# Wilssen_core_v0_205a.net
KiCad netlist of a schematic drawn in EAGLE
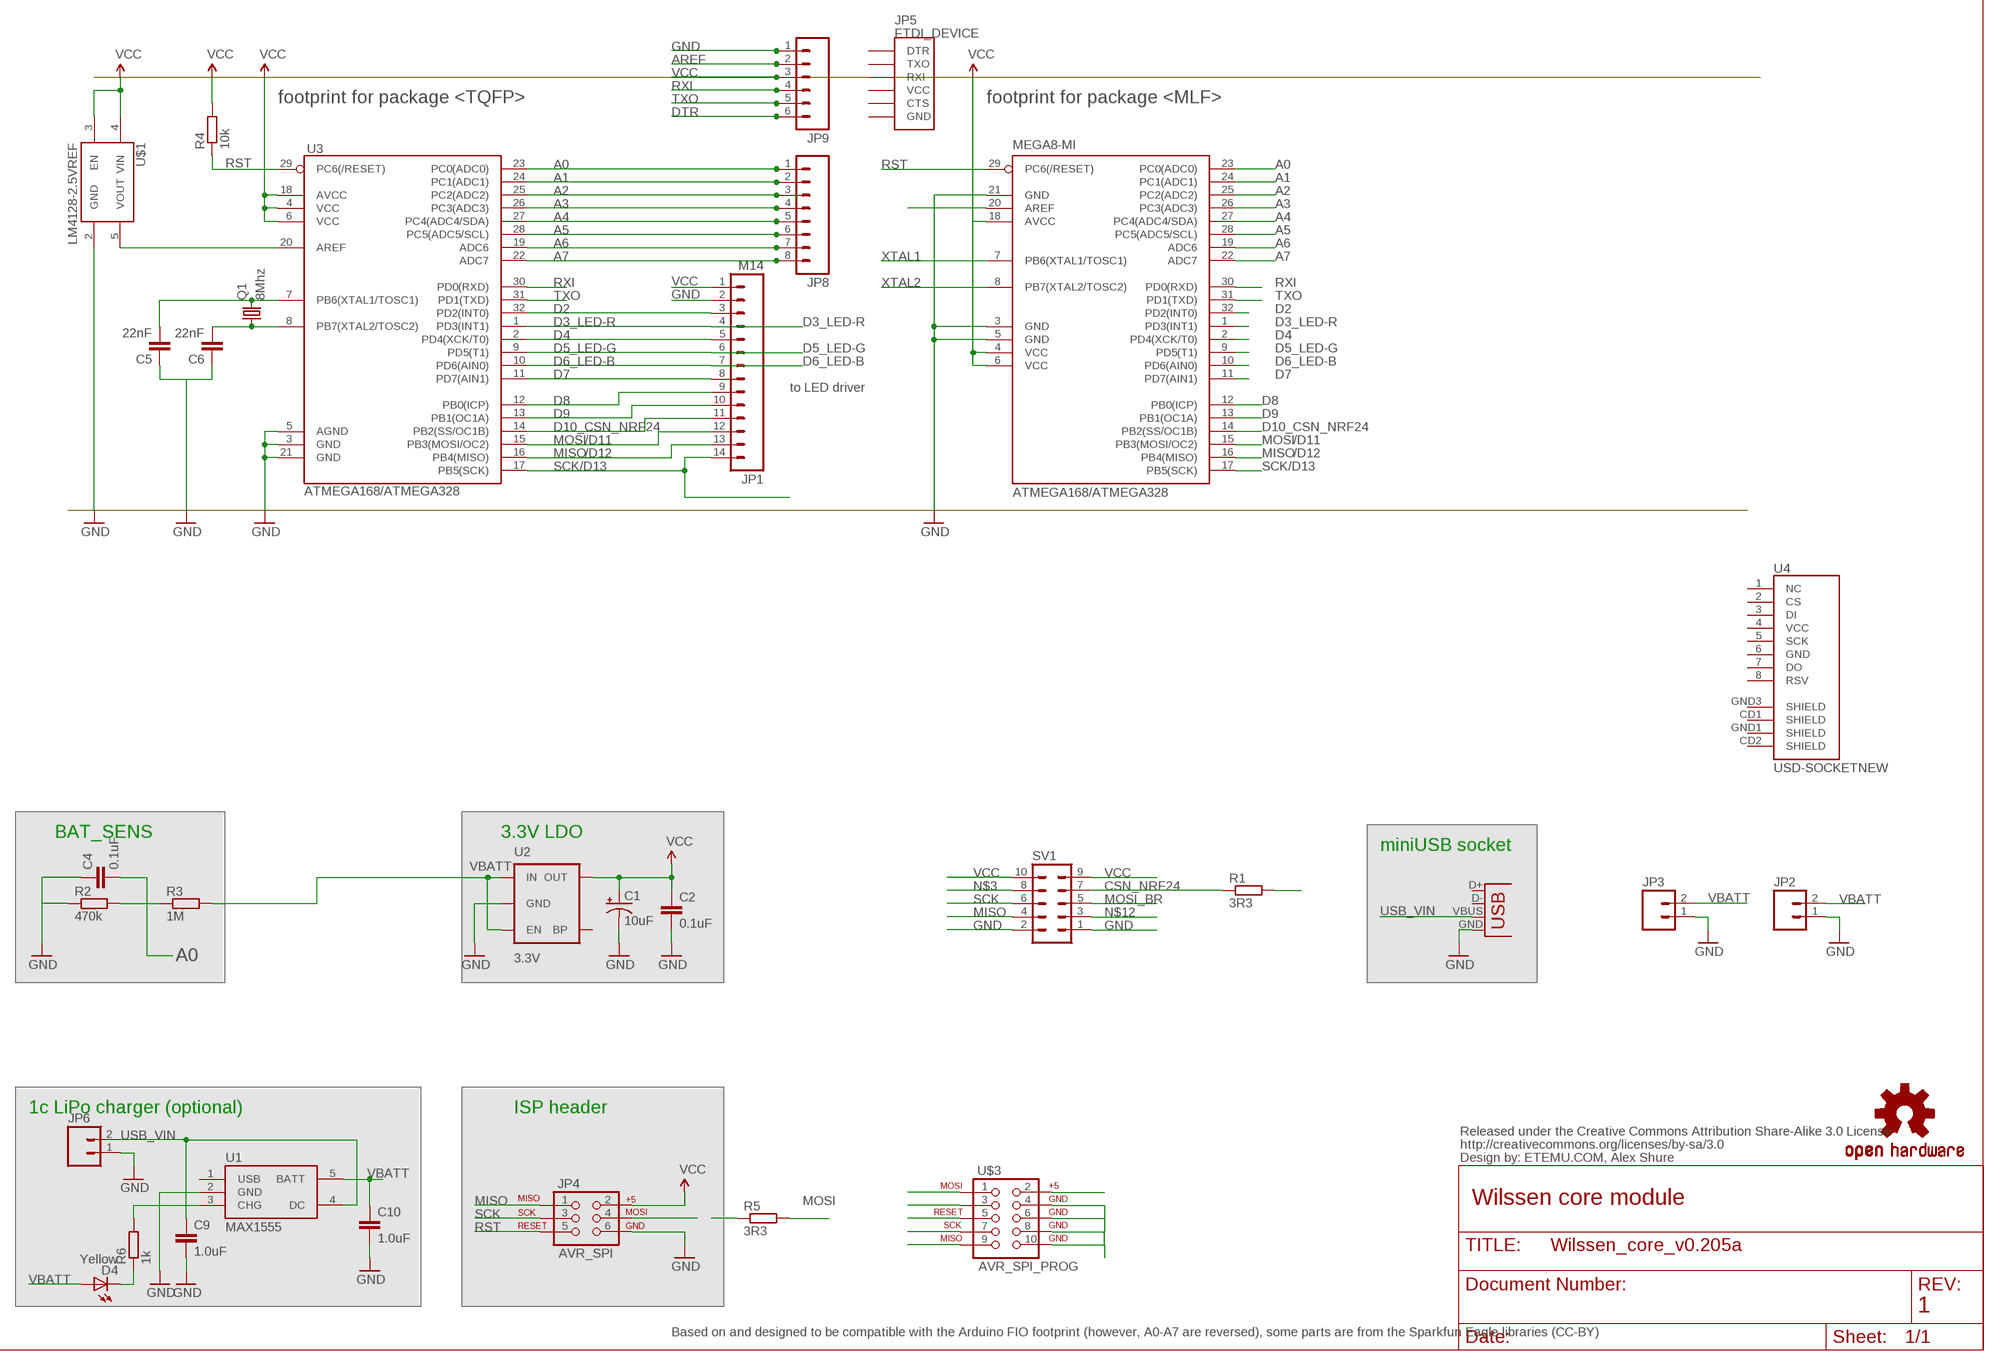
[diagram p0: schematic, sheet 1, part 1 of 2]
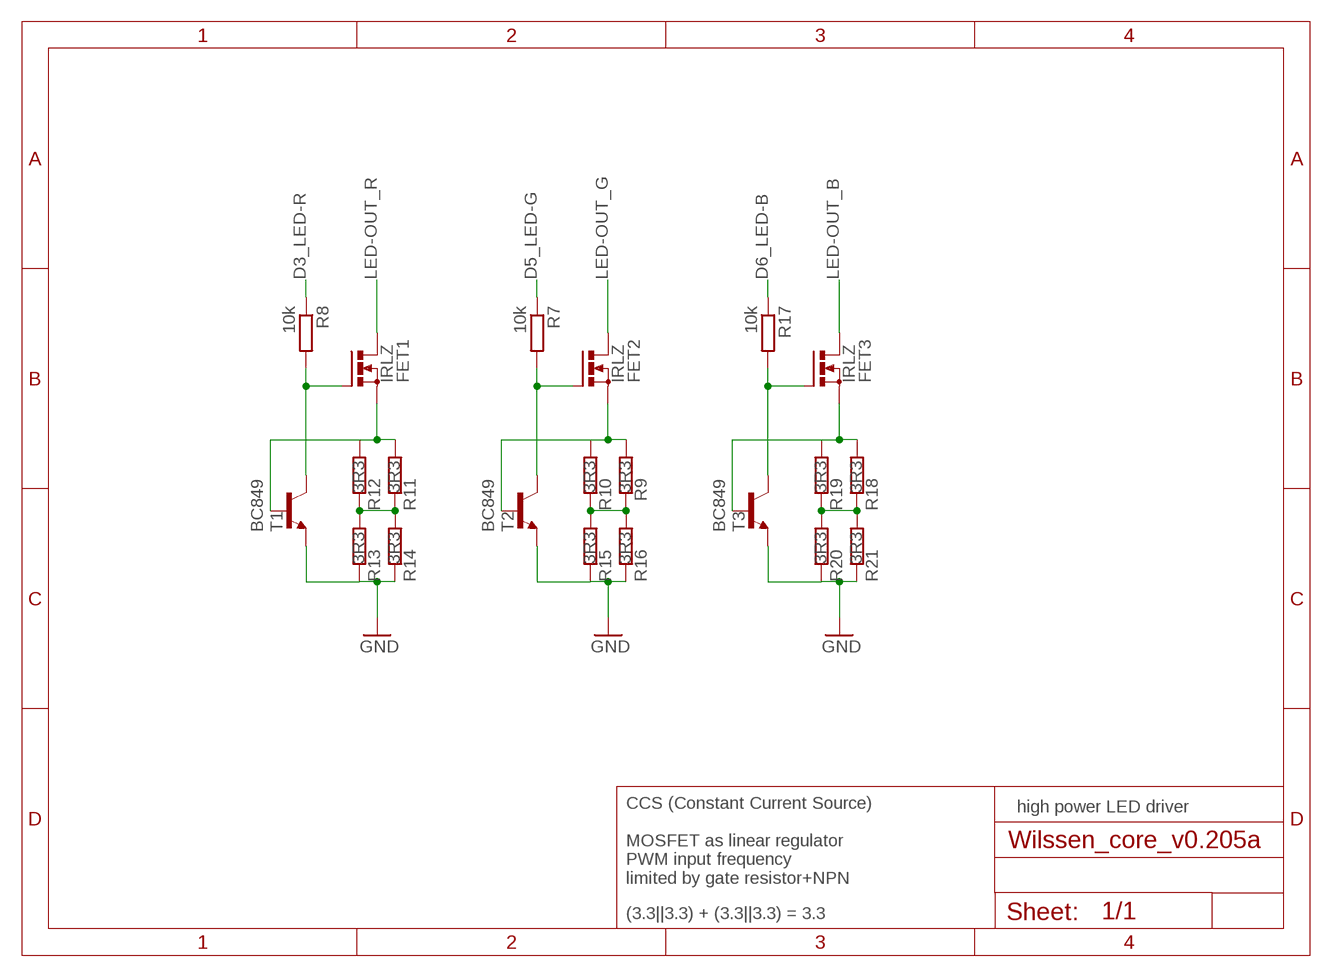
[diagram p1: schematic, sheet 1, part 2 of 2]

(export (version "E")
  (design (tool "Eeschema 10.0.6"))
  (components
    (comp (ref "ATMEGA168/ATMEGA328")
      (value "MEGA8-MI")
      (footprint "eagle-import:MLF32")
      (fields (field (name "MPN") "ATMEGA88PA-MU"))
      (libsource (lib "eagle-import") (part "MEGA8-MI"))
    )
    (comp (ref "C1")
      (value "10uF")
      (footprint "eagle-import:EIA3216")
      (libsource (lib "eagle-import") (part "CAP_POL1206"))
    )
    (comp (ref "C2")
      (value "0.1uF")
      (footprint "eagle-import:0805")
      (libsource (lib "eagle-import") (part "CAP0805"))
    )
    (comp (ref "C4")
      (value "0.1uF")
      (footprint "eagle-import:0805")
      (libsource (lib "eagle-import") (part "CAP0805"))
    )
    (comp (ref "C5")
      (value "22nF")
      (footprint "eagle-import:0805")
      (libsource (lib "eagle-import") (part "CAP0805"))
    )
    (comp (ref "C6")
      (value "22nF")
      (footprint "eagle-import:0805")
      (libsource (lib "eagle-import") (part "CAP0805"))
    )
    (comp (ref "C9")
      (value "1.0uF")
      (footprint "eagle-import:0805")
      (libsource (lib "eagle-import") (part "CAP0805"))
    )
    (comp (ref "C10")
      (value "1.0uF")
      (footprint "eagle-import:0805")
      (libsource (lib "eagle-import") (part "CAP0805"))
    )
    (comp (ref "CC_TEXT1")
      (value "CREATIVE_COMMONS")
      (footprint "eagle-import:CREATIVE_COMMONS")
      (libsource (lib "eagle-import") (part "CREATIVE_COMMONS"))
    )
    (comp (ref "D4")
      (value "Yellow")
      (footprint "eagle-import:LED-0603")
      (libsource (lib "eagle-import") (part "LED0603"))
    )
    (comp (ref "FET1")
      (value "IRLZ")
      (footprint "eagle-import:TO220BV")
      (libsource (lib "eagle-import") (part "PMOSFET_NTO220BV"))
    )
    (comp (ref "FET2")
      (value "IRLZ")
      (footprint "eagle-import:TO220BV")
      (libsource (lib "eagle-import") (part "PMOSFET_NTO220BV"))
    )
    (comp (ref "FET3")
      (value "IRLZ")
      (footprint "eagle-import:TO220BV")
      (libsource (lib "eagle-import") (part "PMOSFET_NTO220BV"))
    )
    (comp (ref "JP1")
      (value "M14")
      (footprint "eagle-import:1X14")
      (libsource (lib "eagle-import") (part "M14"))
    )
    (comp (ref "JP2")
      (value "M02PTH")
      (footprint "eagle-import:1X02")
      (libsource (lib "eagle-import") (part "M02PTH"))
    )
    (comp (ref "JP3")
      (value "M02-JST-2MM-SMT")
      (footprint "eagle-import:S2B-PH")
      (libsource (lib "eagle-import") (part "M02-JST-2MM-SMT"))
    )
    (comp (ref "JP4")
      (value "AVR_SPI")
      (footprint "eagle-import:2X3")
      (libsource (lib "eagle-import") (part "AVR_SPI_PRG_6PTH"))
    )
    (comp (ref "JP5")
      (value "FTDI_DEVICE")
      (footprint "eagle-import:FTDI_DEVICE_SIDE")
      (libsource (lib "eagle-import") (part "FTDI_DEVICE"))
    )
    (comp (ref "JP6")
      (value "M02PTH")
      (footprint "eagle-import:1X02")
      (libsource (lib "eagle-import") (part "M02PTH"))
    )
    (comp (ref "JP8")
      (value "M081X08")
      (footprint "eagle-import:1X08")
      (libsource (lib "eagle-import") (part "M081X08"))
    )
    (comp (ref "JP9")
      (value "M06SIP")
      (footprint "eagle-import:1X06")
      (libsource (lib "eagle-import") (part "M06SIP"))
    )
    (comp (ref "LOGO1")
      (value "OSHW-LOGOS")
      (footprint "eagle-import:OSHW-LOGO-S")
      (libsource (lib "eagle-import") (part "OSHW-LOGOS"))
    )
    (comp (ref "Q1")
      (value "8Mhz")
      (footprint "eagle-import:SM49")
      (libsource (lib "eagle-import") (part "CRYSTALSM49"))
    )
    (comp (ref "R1")
      (value "3R3")
      (footprint "eagle-import:R1206")
      (libsource (lib "eagle-import") (part "R-EU_R1206"))
    )
    (comp (ref "R2")
      (value "470k")
      (footprint "eagle-import:R0805")
      (libsource (lib "eagle-import") (part "R-EU_R0805"))
    )
    (comp (ref "R3")
      (value "1M")
      (footprint "eagle-import:R0805")
      (libsource (lib "eagle-import") (part "R-EU_R0805"))
    )
    (comp (ref "R4")
      (value "10k")
      (footprint "eagle-import:R0805")
      (libsource (lib "eagle-import") (part "R-EU_R0805"))
    )
    (comp (ref "R5")
      (value "3R3")
      (footprint "eagle-import:R1206")
      (libsource (lib "eagle-import") (part "R-EU_R1206"))
    )
    (comp (ref "R6")
      (value "1k")
      (footprint "eagle-import:R0805")
      (libsource (lib "eagle-import") (part "R-EU_R0805"))
    )
    (comp (ref "R7")
      (value "10k")
      (footprint "eagle-import:R0805")
      (libsource (lib "eagle-import") (part "resistor_R-EU_R0805"))
    )
    (comp (ref "R8")
      (value "10k")
      (footprint "eagle-import:R0805")
      (libsource (lib "eagle-import") (part "resistor_R-EU_R0805"))
    )
    (comp (ref "R9")
      (value "3R3")
      (footprint "eagle-import:R1206")
      (libsource (lib "eagle-import") (part "resistor_R-EU_R1206"))
    )
    (comp (ref "R10")
      (value "3R3")
      (footprint "eagle-import:R1206")
      (libsource (lib "eagle-import") (part "resistor_R-EU_R1206"))
    )
    (comp (ref "R11")
      (value "3R3")
      (footprint "eagle-import:R1206")
      (libsource (lib "eagle-import") (part "resistor_R-EU_R1206"))
    )
    (comp (ref "R12")
      (value "3R3")
      (footprint "eagle-import:R1206")
      (libsource (lib "eagle-import") (part "resistor_R-EU_R1206"))
    )
    (comp (ref "R13")
      (value "3R3")
      (footprint "eagle-import:R1206")
      (libsource (lib "eagle-import") (part "resistor_R-EU_R1206"))
    )
    (comp (ref "R14")
      (value "3R3")
      (footprint "eagle-import:R1206")
      (libsource (lib "eagle-import") (part "resistor_R-EU_R1206"))
    )
    (comp (ref "R15")
      (value "3R3")
      (footprint "eagle-import:R1206")
      (libsource (lib "eagle-import") (part "resistor_R-EU_R1206"))
    )
    (comp (ref "R16")
      (value "3R3")
      (footprint "eagle-import:R1206")
      (libsource (lib "eagle-import") (part "resistor_R-EU_R1206"))
    )
    (comp (ref "R17")
      (value "10k")
      (footprint "eagle-import:R0805")
      (libsource (lib "eagle-import") (part "resistor_R-EU_R0805"))
    )
    (comp (ref "R18")
      (value "3R3")
      (footprint "eagle-import:R1206")
      (libsource (lib "eagle-import") (part "resistor_R-EU_R1206"))
    )
    (comp (ref "R19")
      (value "3R3")
      (footprint "eagle-import:R1206")
      (libsource (lib "eagle-import") (part "resistor_R-EU_R1206"))
    )
    (comp (ref "R20")
      (value "3R3")
      (footprint "eagle-import:R1206")
      (libsource (lib "eagle-import") (part "resistor_R-EU_R1206"))
    )
    (comp (ref "R21")
      (value "3R3")
      (footprint "eagle-import:R1206")
      (libsource (lib "eagle-import") (part "resistor_R-EU_R1206"))
    )
    (comp (ref "SV1")
      (value "MA05-2")
      (footprint "eagle-import:MA05-2")
      (libsource (lib "eagle-import") (part "MA05-2"))
    )
    (comp (ref "T1")
      (value "BC849")
      (footprint "eagle-import:SOT23")
      (libsource (lib "eagle-import") (part "BC849"))
    )
    (comp (ref "T2")
      (value "BC849")
      (footprint "eagle-import:SOT23")
      (libsource (lib "eagle-import") (part "BC849"))
    )
    (comp (ref "T3")
      (value "BC849")
      (footprint "eagle-import:SOT23")
      (libsource (lib "eagle-import") (part "BC849"))
    )
    (comp (ref "U$1")
      (value "LM4128-2.5VREF")
      (footprint "eagle-import:SOT23-5")
      (libsource (lib "eagle-import") (part "LM4128-2.5VREF"))
    )
    (comp (ref "U$3")
      (value "AVR_SPI_PROG")
      (footprint "eagle-import:AVR_ICSP")
      (libsource (lib "eagle-import") (part "AVR_SPI_PROG"))
    )
    (comp (ref "U1")
      (value "MAX1555")
      (footprint "eagle-import:SOT23-5")
      (libsource (lib "eagle-import") (part "MAX1555"))
    )
    (comp (ref "U2")
      (value "3.3V")
      (footprint "eagle-import:SOT23-5")
      (libsource (lib "eagle-import") (part "V_REG_LDOSMD"))
    )
    (comp (ref "U3")
      (value "ATMEGA168/ATMEGA328")
      (footprint "eagle-import:TQFP32-08")
      (libsource (lib "eagle-import") (part "ATMEGA168"))
    )
    (comp (ref "U4")
      (value "USD-SOCKETNEW")
      (footprint "eagle-import:MICRO-SD-SOCKET-PP")
      (libsource (lib "eagle-import") (part "USD-SOCKETNEW"))
    )
    (comp (ref "X1")
      (value "USBSMD")
      (footprint "eagle-import:USB-MINIB")
      (libsource (lib "eagle-import") (part "USBSMD"))
    )
  )
  (nets
    (net (code "1") (name "/A0") (class "Default")
      (node (ref "ATMEGA168/ATMEGA328") (pin "23") (pinfunction "PC0(ADC0)_23") (pintype "bidirectional"))
      (node (ref "C4") (pin "2") (pinfunction "2_2") (pintype "passive"))
      (node (ref "JP8") (pin "1") (pinfunction "1_1") (pintype "passive"))
      (node (ref "R2") (pin "2") (pinfunction "2_2") (pintype "passive"))
      (node (ref "R3") (pin "1") (pinfunction "1_1") (pintype "passive"))
      (node (ref "U3") (pin "23") (pinfunction "PC0(ADC0)_23") (pintype "bidirectional"))
    )
    (net (code "2") (name "/A1") (class "Default")
      (node (ref "ATMEGA168/ATMEGA328") (pin "24") (pinfunction "PC1(ADC1)_24") (pintype "bidirectional"))
      (node (ref "JP8") (pin "2") (pinfunction "2_2") (pintype "passive"))
      (node (ref "U3") (pin "24") (pinfunction "PC1(ADC1)_24") (pintype "bidirectional"))
    )
    (net (code "3") (name "/A2") (class "Default")
      (node (ref "ATMEGA168/ATMEGA328") (pin "25") (pinfunction "PC2(ADC2)_25") (pintype "bidirectional"))
      (node (ref "JP8") (pin "3") (pinfunction "3_3") (pintype "passive"))
      (node (ref "U3") (pin "25") (pinfunction "PC2(ADC2)_25") (pintype "bidirectional"))
    )
    (net (code "4") (name "/A3") (class "Default")
      (node (ref "ATMEGA168/ATMEGA328") (pin "26") (pinfunction "PC3(ADC3)_26") (pintype "bidirectional"))
      (node (ref "JP8") (pin "4") (pinfunction "4_4") (pintype "passive"))
      (node (ref "U3") (pin "26") (pinfunction "PC3(ADC3)_26") (pintype "bidirectional"))
    )
    (net (code "5") (name "/A4") (class "Default")
      (node (ref "ATMEGA168/ATMEGA328") (pin "27") (pinfunction "PC4(ADC4/SDA)_27") (pintype "bidirectional"))
      (node (ref "JP8") (pin "5") (pinfunction "5_5") (pintype "passive"))
      (node (ref "U3") (pin "27") (pinfunction "PC4(ADC4/SDA)_27") (pintype "bidirectional"))
    )
    (net (code "6") (name "/A5") (class "Default")
      (node (ref "ATMEGA168/ATMEGA328") (pin "28") (pinfunction "PC5(ADC5/SCL)_28") (pintype "bidirectional"))
      (node (ref "JP8") (pin "6") (pinfunction "6_6") (pintype "passive"))
      (node (ref "U3") (pin "28") (pinfunction "PC5(ADC5/SCL)_28") (pintype "bidirectional"))
    )
    (net (code "7") (name "/A6") (class "Default")
      (node (ref "ATMEGA168/ATMEGA328") (pin "19") (pinfunction "ADC6_19") (pintype "bidirectional"))
      (node (ref "JP8") (pin "7") (pinfunction "7_7") (pintype "passive"))
      (node (ref "U3") (pin "19") (pinfunction "ADC6_19") (pintype "bidirectional"))
    )
    (net (code "8") (name "/A7") (class "Default")
      (node (ref "ATMEGA168/ATMEGA328") (pin "22") (pinfunction "ADC7_22") (pintype "bidirectional"))
      (node (ref "JP8") (pin "8") (pinfunction "8_8") (pintype "passive"))
      (node (ref "U3") (pin "22") (pinfunction "ADC7_22") (pintype "bidirectional"))
    )
    (net (code "9") (name "/AREF") (class "Default")
      (node (ref "ATMEGA168/ATMEGA328") (pin "20") (pinfunction "AREF_20") (pintype "passive"))
      (node (ref "JP9") (pin "2") (pinfunction "2_2") (pintype "passive"))
      (node (ref "U$1") (pin "5") (pinfunction "VOUT_5") (pintype "bidirectional"))
      (node (ref "U3") (pin "20") (pinfunction "AREF_20") (pintype "bidirectional"))
    )
    (net (code "10") (name "/CSN_NRF24") (class "Default")
      (node (ref "R1") (pin "1") (pinfunction "1_1") (pintype "passive"))
      (node (ref "SV1") (pin "7") (pinfunction "7_7") (pintype "passive"))
    )
    (net (code "11") (name "/D2") (class "Default")
      (node (ref "ATMEGA168/ATMEGA328") (pin "32") (pinfunction "PD2(INT0)_32") (pintype "bidirectional"))
      (node (ref "JP1") (pin "3") (pinfunction "3_3") (pintype "passive"))
      (node (ref "U3") (pin "32") (pinfunction "PD2(INT0)_32") (pintype "bidirectional"))
    )
    (net (code "12") (name "/D3_LED-R") (class "Default")
      (node (ref "ATMEGA168/ATMEGA328") (pin "1") (pinfunction "PD3(INT1)_1") (pintype "bidirectional"))
      (node (ref "JP1") (pin "4") (pinfunction "4_4") (pintype "passive"))
      (node (ref "R8") (pin "1") (pinfunction "1_1") (pintype "passive"))
      (node (ref "U3") (pin "1") (pinfunction "PD3(INT1)_1") (pintype "bidirectional"))
    )
    (net (code "13") (name "/D4") (class "Default")
      (node (ref "ATMEGA168/ATMEGA328") (pin "2") (pinfunction "PD4(XCK/T0)_2") (pintype "bidirectional"))
      (node (ref "JP1") (pin "5") (pinfunction "5_5") (pintype "passive"))
      (node (ref "U3") (pin "2") (pinfunction "PD4(XCK/T0)_2") (pintype "bidirectional"))
    )
    (net (code "14") (name "/D5_LED-G") (class "Default")
      (node (ref "ATMEGA168/ATMEGA328") (pin "9") (pinfunction "PD5(T1)_9") (pintype "bidirectional"))
      (node (ref "JP1") (pin "6") (pinfunction "6_6") (pintype "passive"))
      (node (ref "R7") (pin "1") (pinfunction "1_1") (pintype "passive"))
      (node (ref "U3") (pin "9") (pinfunction "PD5(T1)_9") (pintype "bidirectional"))
    )
    (net (code "15") (name "/D6_LED-B") (class "Default")
      (node (ref "ATMEGA168/ATMEGA328") (pin "10") (pinfunction "PD6(AIN0)_10") (pintype "bidirectional"))
      (node (ref "JP1") (pin "7") (pinfunction "7_7") (pintype "passive"))
      (node (ref "R17") (pin "1") (pinfunction "1_1") (pintype "passive"))
      (node (ref "U3") (pin "10") (pinfunction "PD6(AIN0)_10") (pintype "bidirectional"))
    )
    (net (code "16") (name "/D7") (class "Default")
      (node (ref "ATMEGA168/ATMEGA328") (pin "11") (pinfunction "PD7(AIN1)_11") (pintype "bidirectional"))
      (node (ref "JP1") (pin "8") (pinfunction "8_8") (pintype "passive"))
      (node (ref "U3") (pin "11") (pinfunction "PD7(AIN1)_11") (pintype "bidirectional"))
    )
    (net (code "17") (name "/D8") (class "Default")
      (node (ref "ATMEGA168/ATMEGA328") (pin "12") (pinfunction "PB0(ICP)_12") (pintype "bidirectional"))
      (node (ref "JP1") (pin "9") (pinfunction "9_9") (pintype "passive"))
      (node (ref "U3") (pin "12") (pinfunction "PB0(ICP)_12") (pintype "bidirectional"))
    )
    (net (code "18") (name "/D9") (class "Default")
      (node (ref "ATMEGA168/ATMEGA328") (pin "13") (pinfunction "PB1(OC1A)_13") (pintype "bidirectional"))
      (node (ref "JP1") (pin "10") (pinfunction "10_10") (pintype "passive"))
      (node (ref "U3") (pin "13") (pinfunction "PB1(OC1A)_13") (pintype "bidirectional"))
    )
    (net (code "19") (name "/D10_CSN_NRF24") (class "Default")
      (node (ref "ATMEGA168/ATMEGA328") (pin "14") (pinfunction "PB2(SS/OC1B)_14") (pintype "bidirectional"))
      (node (ref "JP1") (pin "11") (pinfunction "11_11") (pintype "passive"))
      (node (ref "R1") (pin "2") (pinfunction "2_2") (pintype "passive"))
      (node (ref "U3") (pin "14") (pinfunction "PB2(SS/OC1B)_14") (pintype "bidirectional"))
    )
    (net (code "20") (name "/DTR") (class "Default")
      (node (ref "JP9") (pin "6") (pinfunction "6_6") (pintype "passive"))
    )
    (net (code "21") (name "/LED-OUT_B") (class "Default")
      (node (ref "FET3") (pin "D") (pinfunction "D_D") (pintype "passive"))
    )
    (net (code "22") (name "/LED-OUT_G") (class "Default")
      (node (ref "FET2") (pin "D") (pinfunction "D_D") (pintype "passive"))
    )
    (net (code "23") (name "/LED-OUT_R") (class "Default")
      (node (ref "FET1") (pin "D") (pinfunction "D_D") (pintype "passive"))
    )
    (net (code "24") (name "/MISO") (class "Default")
      (node (ref "ATMEGA168/ATMEGA328") (pin "16") (pinfunction "PB4(MISO)_16") (pintype "bidirectional"))
      (node (ref "JP1") (pin "13") (pinfunction "13_13") (pintype "passive"))
      (node (ref "JP4") (pin "1") (pinfunction "1_1") (pintype "passive"))
      (node (ref "SV1") (pin "4") (pinfunction "4_4") (pintype "passive"))
      (node (ref "U$3") (pin "9") (pinfunction "9_9") (pintype "passive"))
      (node (ref "U3") (pin "16") (pinfunction "PB4(MISO)_16") (pintype "bidirectional"))
    )
    (net (code "25") (name "/MOSI") (class "Default")
      (node (ref "ATMEGA168/ATMEGA328") (pin "15") (pinfunction "PB3(MOSI/OC2)_15") (pintype "bidirectional"))
      (node (ref "JP1") (pin "12") (pinfunction "12_12") (pintype "passive"))
      (node (ref "JP4") (pin "4") (pinfunction "4_4") (pintype "passive"))
      (node (ref "R5") (pin "2") (pinfunction "2_2") (pintype "passive"))
      (node (ref "U$3") (pin "1") (pinfunction "1_1") (pintype "passive"))
      (node (ref "U3") (pin "15") (pinfunction "PB3(MOSI/OC2)_15") (pintype "bidirectional"))
    )
    (net (code "26") (name "/MOSI_BR") (class "Default")
      (node (ref "SV1") (pin "5") (pinfunction "5_5") (pintype "passive"))
    )
    (net (code "27") (name "/N$3") (class "Default")
      (node (ref "SV1") (pin "8") (pinfunction "8_8") (pintype "passive"))
    )
    (net (code "28") (name "/N$12") (class "Default")
      (node (ref "SV1") (pin "3") (pinfunction "3_3") (pintype "passive"))
    )
    (net (code "29") (name "/RST") (class "Default")
      (node (ref "ATMEGA168/ATMEGA328") (pin "29") (pinfunction "PC6(/RESET)_29") (pintype "bidirectional"))
      (node (ref "JP4") (pin "5") (pinfunction "5_5") (pintype "passive"))
      (node (ref "R4") (pin "1") (pinfunction "1_1") (pintype "passive"))
      (node (ref "U$3") (pin "5") (pinfunction "5_5") (pintype "passive"))
      (node (ref "U3") (pin "29") (pinfunction "PC6(/RESET)_29") (pintype "bidirectional"))
    )
    (net (code "30") (name "/RXI") (class "Default")
      (node (ref "ATMEGA168/ATMEGA328") (pin "30") (pinfunction "PD0(RXD)_30") (pintype "bidirectional"))
      (node (ref "JP9") (pin "4") (pinfunction "4_4") (pintype "passive"))
      (node (ref "U3") (pin "30") (pinfunction "PD0(RXD)_30") (pintype "bidirectional"))
    )
    (net (code "31") (name "/SCK") (class "Default")
      (node (ref "ATMEGA168/ATMEGA328") (pin "17") (pinfunction "PB5(SCK)_17") (pintype "bidirectional"))
      (node (ref "JP1") (pin "14") (pinfunction "14_14") (pintype "passive"))
      (node (ref "JP4") (pin "3") (pinfunction "3_3") (pintype "passive"))
      (node (ref "SV1") (pin "6") (pinfunction "6_6") (pintype "passive"))
      (node (ref "U$3") (pin "7") (pinfunction "7_7") (pintype "passive"))
      (node (ref "U3") (pin "17") (pinfunction "PB5(SCK)_17") (pintype "bidirectional"))
    )
    (net (code "32") (name "/TXO") (class "Default")
      (node (ref "ATMEGA168/ATMEGA328") (pin "31") (pinfunction "PD1(TXD)_31") (pintype "bidirectional"))
      (node (ref "JP9") (pin "5") (pinfunction "5_5") (pintype "passive"))
      (node (ref "U3") (pin "31") (pinfunction "PD1(TXD)_31") (pintype "bidirectional"))
    )
    (net (code "33") (name "/USB_VIN") (class "Default")
      (node (ref "C9") (pin "1") (pinfunction "1_1") (pintype "passive"))
      (node (ref "JP6") (pin "2") (pinfunction "2_2") (pintype "passive"))
      (node (ref "U1") (pin "4") (pinfunction "DC_4") (pintype "bidirectional"))
      (node (ref "X1") (pin "VBUS") (pinfunction "VBUS_VBUS") (pintype "bidirectional"))
    )
    (net (code "34") (name "/VBATT") (class "Default")
      (node (ref "C10") (pin "1") (pinfunction "1_1") (pintype "passive"))
      (node (ref "D4") (pin "A") (pinfunction "A_A") (pintype "passive"))
      (node (ref "JP2") (pin "2") (pinfunction "2_2") (pintype "passive"))
      (node (ref "JP3") (pin "2") (pinfunction "2_2") (pintype "passive"))
      (node (ref "R3") (pin "2") (pinfunction "2_2") (pintype "passive"))
      (node (ref "U1") (pin "5") (pinfunction "BATT_5") (pintype "bidirectional"))
      (node (ref "U2") (pin "1") (pinfunction "IN_1") (pintype "input"))
      (node (ref "U2") (pin "3") (pinfunction "EN_3") (pintype "input"))
    )
    (net (code "35") (name "/XTAL1") (class "Default")
      (node (ref "ATMEGA168/ATMEGA328") (pin "7") (pinfunction "PB6(XTAL1/TOSC1)_7") (pintype "bidirectional"))
      (node (ref "C5") (pin "2") (pinfunction "2_2") (pintype "passive"))
      (node (ref "Q1") (pin "2") (pinfunction "2_2") (pintype "passive"))
      (node (ref "U3") (pin "7") (pinfunction "PB6(XTAL1/TOSC1)_7") (pintype "bidirectional"))
    )
    (net (code "36") (name "/XTAL2") (class "Default")
      (node (ref "ATMEGA168/ATMEGA328") (pin "8") (pinfunction "PB7(XTAL2/TOSC2)_8") (pintype "bidirectional"))
      (node (ref "C6") (pin "2") (pinfunction "2_2") (pintype "passive"))
      (node (ref "Q1") (pin "1") (pinfunction "1_1") (pintype "passive"))
      (node (ref "U3") (pin "8") (pinfunction "PB7(XTAL2/TOSC2)_8") (pintype "bidirectional"))
    )
    (net (code "37") (name "GND") (class "Default")
      (node (ref "ATMEGA168/ATMEGA328") (pin "21") (pinfunction "GND_21") (pintype "power_in"))
      (node (ref "ATMEGA168/ATMEGA328") (pin "3") (pinfunction "GND_3") (pintype "power_in"))
      (node (ref "ATMEGA168/ATMEGA328") (pin "5") (pinfunction "GND_5") (pintype "power_in"))
      (node (ref "C1") (pin "C") (pinfunction "-_C") (pintype "passive"))
      (node (ref "C10") (pin "2") (pinfunction "2_2") (pintype "passive"))
      (node (ref "C2") (pin "2") (pinfunction "2_2") (pintype "passive"))
      (node (ref "C4") (pin "1") (pinfunction "1_1") (pintype "passive"))
      (node (ref "C5") (pin "1") (pinfunction "1_1") (pintype "passive"))
      (node (ref "C6") (pin "1") (pinfunction "1_1") (pintype "passive"))
      (node (ref "C9") (pin "2") (pinfunction "2_2") (pintype "passive"))
      (node (ref "JP1") (pin "2") (pinfunction "2_2") (pintype "passive"))
      (node (ref "JP2") (pin "1") (pinfunction "1_1") (pintype "passive"))
      (node (ref "JP3") (pin "1") (pinfunction "1_1") (pintype "passive"))
      (node (ref "JP4") (pin "6") (pinfunction "6_6") (pintype "passive"))
      (node (ref "JP6") (pin "1") (pinfunction "1_1") (pintype "passive"))
      (node (ref "JP9") (pin "1") (pinfunction "1_1") (pintype "passive"))
      (node (ref "R13") (pin "2") (pinfunction "2_2") (pintype "passive"))
      (node (ref "R14") (pin "2") (pinfunction "2_2") (pintype "passive"))
      (node (ref "R15") (pin "2") (pinfunction "2_2") (pintype "passive"))
      (node (ref "R16") (pin "2") (pinfunction "2_2") (pintype "passive"))
      (node (ref "R2") (pin "1") (pinfunction "1_1") (pintype "passive"))
      (node (ref "R20") (pin "2") (pinfunction "2_2") (pintype "passive"))
      (node (ref "R21") (pin "2") (pinfunction "2_2") (pintype "passive"))
      (node (ref "SV1") (pin "1") (pinfunction "1_1") (pintype "passive"))
      (node (ref "SV1") (pin "2") (pinfunction "2_2") (pintype "passive"))
      (node (ref "T1") (pin "2") (pinfunction "E_2") (pintype "passive"))
      (node (ref "T2") (pin "2") (pinfunction "E_2") (pintype "passive"))
      (node (ref "T3") (pin "2") (pinfunction "E_2") (pintype "passive"))
      (node (ref "U$1") (pin "2") (pinfunction "GND_2") (pintype "bidirectional"))
      (node (ref "U$3") (pin "10") (pinfunction "10_10") (pintype "passive"))
      (node (ref "U$3") (pin "4") (pinfunction "4_4") (pintype "passive"))
      (node (ref "U$3") (pin "6") (pinfunction "6_6") (pintype "passive"))
      (node (ref "U$3") (pin "8") (pinfunction "8_8") (pintype "passive"))
      (node (ref "U1") (pin "2") (pinfunction "GND_2") (pintype "bidirectional"))
      (node (ref "U2") (pin "2") (pinfunction "GND_2") (pintype "input"))
      (node (ref "U3") (pin "21") (pinfunction "GND_21") (pintype "bidirectional"))
      (node (ref "U3") (pin "3") (pinfunction "GND_3") (pintype "bidirectional"))
      (node (ref "U3") (pin "5") (pinfunction "AGND_5") (pintype "bidirectional"))
      (node (ref "X1") (pin "GND") (pinfunction "GND_GND") (pintype "bidirectional"))
    )
    (net (code "38") (name "Net-(D4-PadC)") (class "Default")
      (node (ref "D4") (pin "C") (pinfunction "C_C") (pintype "passive"))
      (node (ref "R6") (pin "1") (pinfunction "1_1") (pintype "passive"))
    )
    (net (code "39") (name "Net-(R10-Pad2)") (class "Default")
      (node (ref "R10") (pin "2") (pinfunction "2_2") (pintype "passive"))
      (node (ref "R15") (pin "1") (pinfunction "1_1") (pintype "passive"))
      (node (ref "R16") (pin "1") (pinfunction "1_1") (pintype "passive"))
      (node (ref "R9") (pin "2") (pinfunction "2_2") (pintype "passive"))
    )
    (net (code "40") (name "Net-(R11-Pad2)") (class "Default")
      (node (ref "R11") (pin "2") (pinfunction "2_2") (pintype "passive"))
      (node (ref "R12") (pin "2") (pinfunction "2_2") (pintype "passive"))
      (node (ref "R13") (pin "1") (pinfunction "1_1") (pintype "passive"))
      (node (ref "R14") (pin "1") (pinfunction "1_1") (pintype "passive"))
    )
    (net (code "41") (name "Net-(R18-Pad2)") (class "Default")
      (node (ref "R18") (pin "2") (pinfunction "2_2") (pintype "passive"))
      (node (ref "R19") (pin "2") (pinfunction "2_2") (pintype "passive"))
      (node (ref "R20") (pin "1") (pinfunction "1_1") (pintype "passive"))
      (node (ref "R21") (pin "1") (pinfunction "1_1") (pintype "passive"))
    )
    (net (code "42") (name "Net-(T1-B)") (class "Default")
      (node (ref "FET1") (pin "S") (pinfunction "S_S") (pintype "passive"))
      (node (ref "R11") (pin "1") (pinfunction "1_1") (pintype "passive"))
      (node (ref "R12") (pin "1") (pinfunction "1_1") (pintype "passive"))
      (node (ref "T1") (pin "1") (pinfunction "B_1") (pintype "passive"))
    )
    (net (code "43") (name "Net-(T1-C)") (class "Default")
      (node (ref "FET1") (pin "G") (pinfunction "G_G") (pintype "passive"))
      (node (ref "R8") (pin "2") (pinfunction "2_2") (pintype "passive"))
      (node (ref "T1") (pin "3") (pinfunction "C_3") (pintype "passive"))
    )
    (net (code "44") (name "Net-(T2-B)") (class "Default")
      (node (ref "FET2") (pin "S") (pinfunction "S_S") (pintype "passive"))
      (node (ref "R10") (pin "1") (pinfunction "1_1") (pintype "passive"))
      (node (ref "R9") (pin "1") (pinfunction "1_1") (pintype "passive"))
      (node (ref "T2") (pin "1") (pinfunction "B_1") (pintype "passive"))
    )
    (net (code "45") (name "Net-(T2-C)") (class "Default")
      (node (ref "FET2") (pin "G") (pinfunction "G_G") (pintype "passive"))
      (node (ref "R7") (pin "2") (pinfunction "2_2") (pintype "passive"))
      (node (ref "T2") (pin "3") (pinfunction "C_3") (pintype "passive"))
    )
    (net (code "46") (name "Net-(T3-B)") (class "Default")
      (node (ref "FET3") (pin "S") (pinfunction "S_S") (pintype "passive"))
      (node (ref "R18") (pin "1") (pinfunction "1_1") (pintype "passive"))
      (node (ref "R19") (pin "1") (pinfunction "1_1") (pintype "passive"))
      (node (ref "T3") (pin "1") (pinfunction "B_1") (pintype "passive"))
    )
    (net (code "47") (name "Net-(T3-C)") (class "Default")
      (node (ref "FET3") (pin "G") (pinfunction "G_G") (pintype "passive"))
      (node (ref "R17") (pin "2") (pinfunction "2_2") (pintype "passive"))
      (node (ref "T3") (pin "3") (pinfunction "C_3") (pintype "passive"))
    )
    (net (code "48") (name "Net-(U1-CHG)") (class "Default")
      (node (ref "R6") (pin "2") (pinfunction "2_2") (pintype "passive"))
      (node (ref "U1") (pin "3") (pinfunction "CHG_3") (pintype "bidirectional"))
    )
    (net (code "49") (name "VCC") (class "Default")
      (node (ref "ATMEGA168/ATMEGA328") (pin "18") (pinfunction "AVCC_18") (pintype "power_in"))
      (node (ref "ATMEGA168/ATMEGA328") (pin "4") (pinfunction "VCC_4") (pintype "power_in"))
      (node (ref "ATMEGA168/ATMEGA328") (pin "6") (pinfunction "VCC_6") (pintype "power_in"))
      (node (ref "C1") (pin "A") (pinfunction "+_A") (pintype "passive"))
      (node (ref "C2") (pin "1") (pinfunction "1_1") (pintype "passive"))
      (node (ref "JP1") (pin "1") (pinfunction "1_1") (pintype "passive"))
      (node (ref "JP4") (pin "2") (pinfunction "2_2") (pintype "passive"))
      (node (ref "JP9") (pin "3") (pinfunction "3_3") (pintype "passive"))
      (node (ref "R4") (pin "2") (pinfunction "2_2") (pintype "passive"))
      (node (ref "SV1") (pin "10") (pinfunction "10_10") (pintype "passive"))
      (node (ref "SV1") (pin "9") (pinfunction "9_9") (pintype "passive"))
      (node (ref "U$1") (pin "3") (pinfunction "EN_3") (pintype "bidirectional"))
      (node (ref "U$1") (pin "4") (pinfunction "VIN_4") (pintype "bidirectional"))
      (node (ref "U$3") (pin "2") (pinfunction "2_2") (pintype "passive"))
      (node (ref "U2") (pin "5") (pinfunction "OUT_5") (pintype "passive"))
      (node (ref "U3") (pin "18") (pinfunction "AVCC_18") (pintype "bidirectional"))
      (node (ref "U3") (pin "4") (pinfunction "VCC_4") (pintype "bidirectional"))
      (node (ref "U3") (pin "6") (pinfunction "VCC_6") (pintype "bidirectional"))
    )
    (net (code "50") (name "unconnected-(JP5-CTS-PadP$5)") (class "Default")
      (node (ref "JP5") (pin "P$5") (pinfunction "CTS_P$5") (pintype "bidirectional"))
    )
    (net (code "51") (name "unconnected-(JP5-DTR-PadP$1)") (class "Default")
      (node (ref "JP5") (pin "P$1") (pinfunction "DTR_P$1") (pintype "bidirectional"))
    )
    (net (code "52") (name "unconnected-(JP5-GND-PadP$6)") (class "Default")
      (node (ref "JP5") (pin "P$6") (pinfunction "GND_P$6") (pintype "bidirectional"))
    )
    (net (code "53") (name "unconnected-(JP5-RXI-PadP$3)") (class "Default")
      (node (ref "JP5") (pin "P$3") (pinfunction "RXI_P$3") (pintype "bidirectional"))
    )
    (net (code "54") (name "unconnected-(JP5-TXO-PadP$2)") (class "Default")
      (node (ref "JP5") (pin "P$2") (pinfunction "TXO_P$2") (pintype "bidirectional"))
    )
    (net (code "55") (name "unconnected-(JP5-VCC-PadP$4)") (class "Default")
      (node (ref "JP5") (pin "P$4") (pinfunction "VCC_P$4") (pintype "bidirectional"))
    )
    (net (code "56") (name "unconnected-(R5-Pad1)") (class "Default")
      (node (ref "R5") (pin "1") (pinfunction "1_1") (pintype "passive"))
    )
    (net (code "57") (name "unconnected-(U$3-Pad3)") (class "Default")
      (node (ref "U$3") (pin "3") (pinfunction "3_3") (pintype "passive"))
    )
    (net (code "58") (name "unconnected-(U1-USB-Pad1)") (class "Default")
      (node (ref "U1") (pin "1") (pinfunction "USB_1") (pintype "bidirectional"))
    )
    (net (code "59") (name "unconnected-(U2-BP-Pad4)") (class "Default")
      (node (ref "U2") (pin "4") (pinfunction "BP_4") (pintype "input"))
    )
    (net (code "60") (name "unconnected-(U4-CS-Pad2)") (class "Default")
      (node (ref "U4") (pin "2") (pinfunction "CS_2") (pintype "bidirectional"))
    )
    (net (code "61") (name "unconnected-(U4-DI-Pad3)") (class "Default")
      (node (ref "U4") (pin "3") (pinfunction "DI_3") (pintype "bidirectional"))
    )
    (net (code "62") (name "unconnected-(U4-DO-Pad7)") (class "Default")
      (node (ref "U4") (pin "7") (pinfunction "DO_7") (pintype "bidirectional"))
    )
    (net (code "63") (name "unconnected-(U4-GND-Pad6)") (class "Default")
      (node (ref "U4") (pin "6") (pinfunction "GND_6") (pintype "bidirectional"))
    )
    (net (code "64") (name "unconnected-(U4-NC-Pad1)") (class "Default")
      (node (ref "U4") (pin "1") (pinfunction "NC_1") (pintype "bidirectional"))
    )
    (net (code "65") (name "unconnected-(U4-RSV-Pad8)") (class "Default")
      (node (ref "U4") (pin "8") (pinfunction "RSV_8") (pintype "bidirectional"))
    )
    (net (code "66") (name "unconnected-(U4-SCK-Pad5)") (class "Default")
      (node (ref "U4") (pin "5") (pinfunction "SCK_5") (pintype "bidirectional"))
    )
    (net (code "67") (name "unconnected-(U4-SHIELD-PadCD1)") (class "Default")
      (node (ref "U4") (pin "CD1") (pinfunction "SHIELD_CD1") (pintype "bidirectional"))
    )
    (net (code "68") (name "unconnected-(U4-SHIELD-PadCD2)") (class "Default")
      (node (ref "U4") (pin "CD2") (pinfunction "SHIELD_CD2") (pintype "bidirectional"))
    )
    (net (code "69") (name "unconnected-(U4-SHIELD-PadGND1)") (class "Default")
      (node (ref "U4") (pin "GND1") (pinfunction "SHIELD_GND1") (pintype "bidirectional"))
    )
    (net (code "70") (name "unconnected-(U4-SHIELD-PadGND3)") (class "Default")
      (node (ref "U4") (pin "GND3") (pinfunction "SHIELD_GND3") (pintype "bidirectional"))
    )
    (net (code "71") (name "unconnected-(U4-VCC-Pad4)") (class "Default")
      (node (ref "U4") (pin "4") (pinfunction "VCC_4") (pintype "bidirectional"))
    )
    (net (code "72") (name "unconnected-(X1-PadD+)") (class "Default")
      (node (ref "X1") (pin "D+") (pinfunction "D+_D+") (pintype "bidirectional"))
    )
    (net (code "73") (name "unconnected-(X1-PadD-)") (class "Default")
      (node (ref "X1") (pin "D-") (pinfunction "D-_D-") (pintype "bidirectional"))
    )
  )
)
